# respirho2pilev2.net
KiCad netlist of a schematic drawn in EAGLE
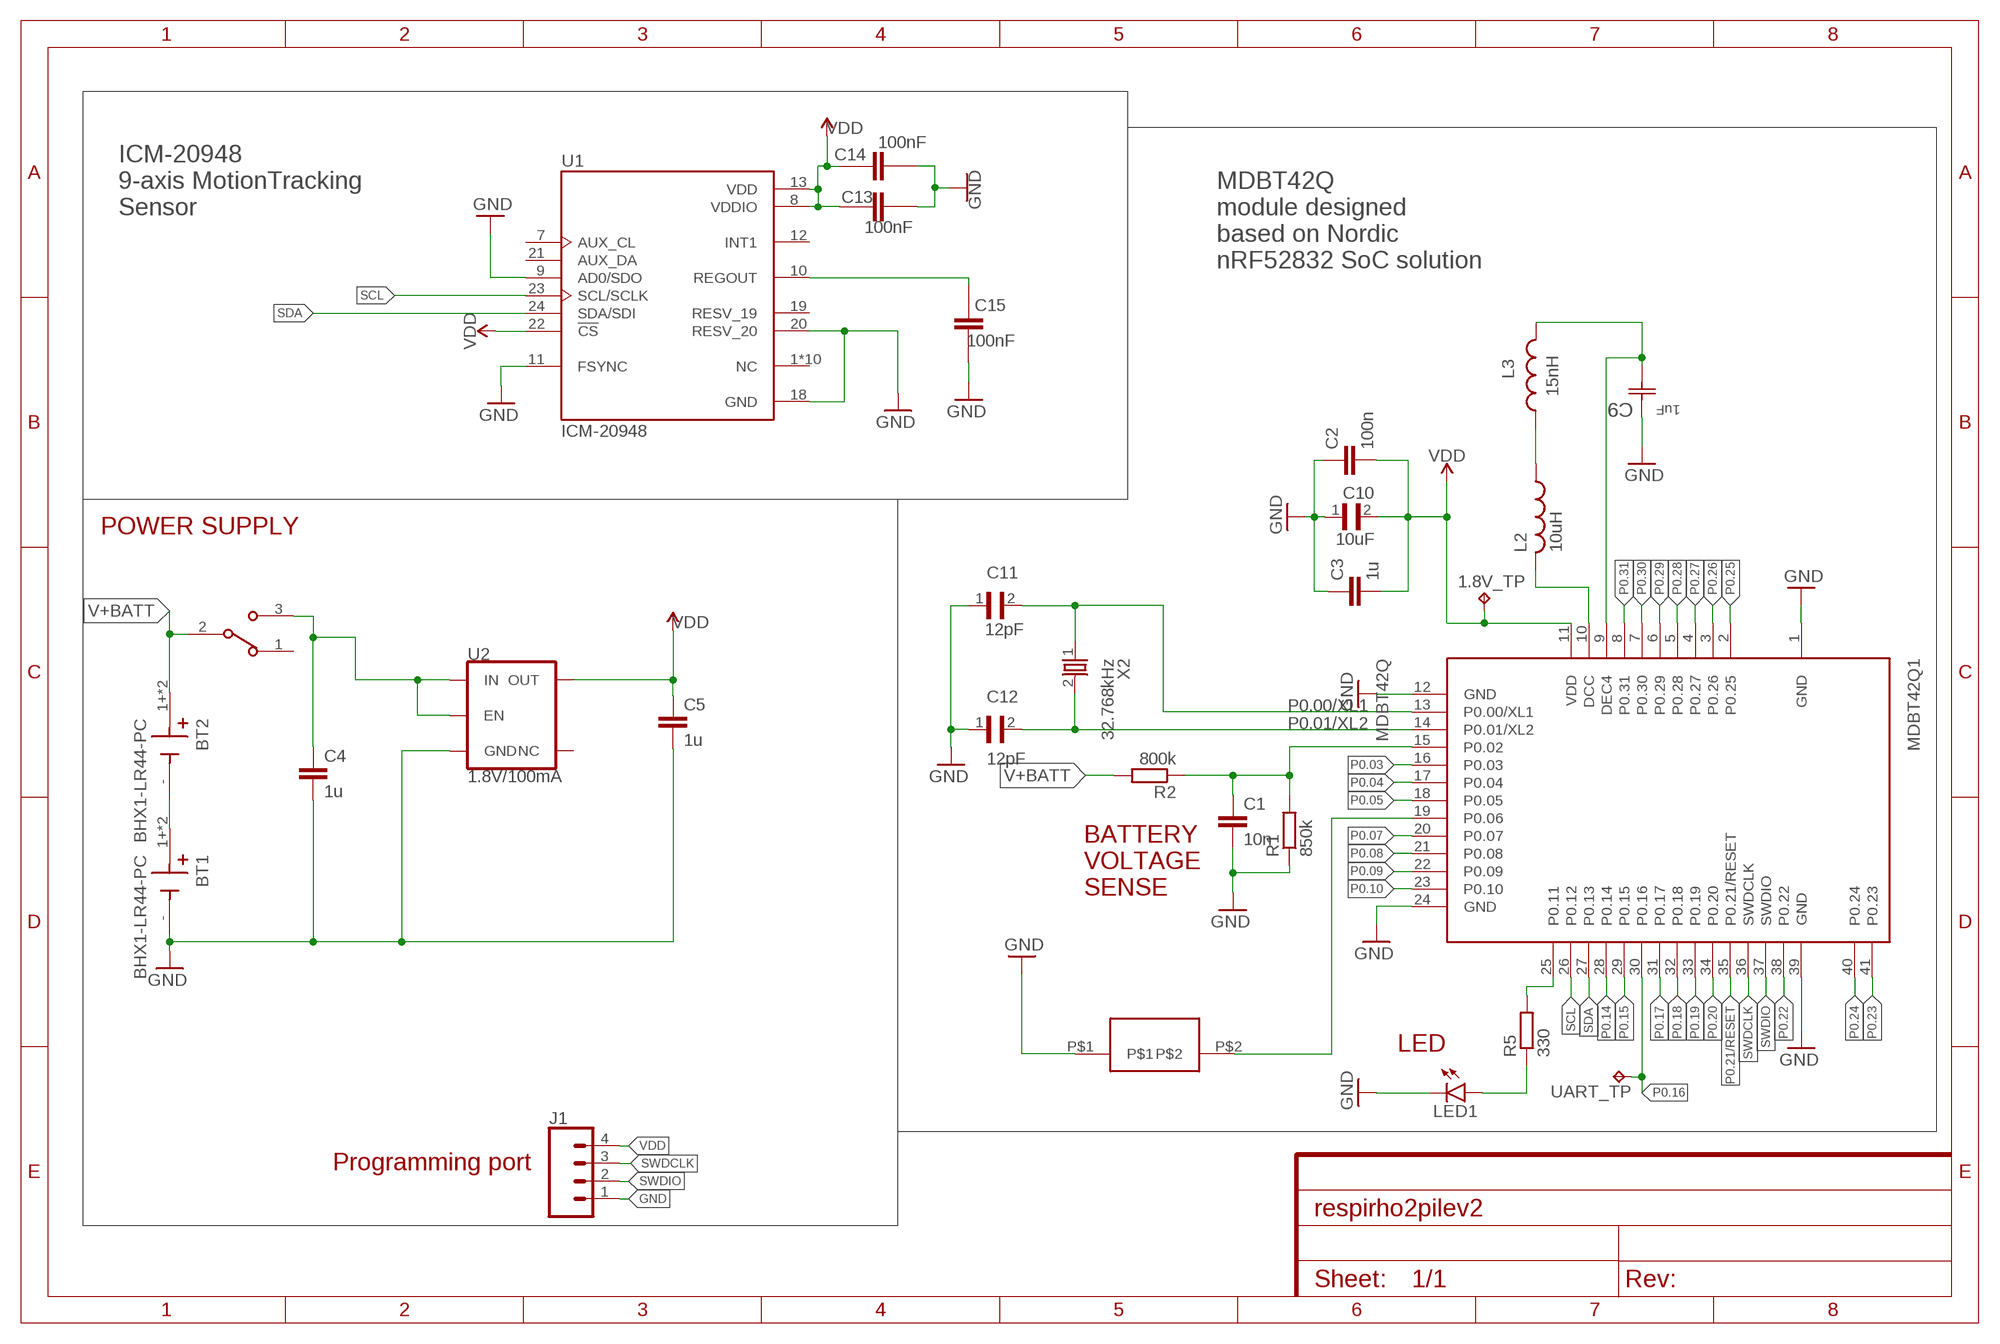
[diagram p0: schematic, sheet 1]

(export (version "E")
  (design (tool "Eeschema 10.0.6"))
  (components
    (comp (ref "1.8V_TP")
      (value "TPB1,27")
      (footprint "eagle-import:B1,27")
      (libsource (lib "eagle-import") (part "TPB1,27"))
    )
    (comp (ref "BT1")
      (value "BHX1-LR44-PC")
      (footprint "eagle-import:BAT_BHX1-LR44-PC")
      (fields (field (name "DIGI-KEY_PART_NUMBER") "BHX1-LR44-PC-G-ND") (field (name "MF") "MPD"))
      (libsource (lib "eagle-import") (part "BHX1-LR44-PC"))
    )
    (comp (ref "BT2")
      (value "BHX1-LR44-PC")
      (footprint "eagle-import:BAT_BHX1-LR44-PC")
      (fields (field (name "DIGI-KEY_PART_NUMBER") "BHX1-LR44-PC-G-ND") (field (name "MF") "MPD"))
      (libsource (lib "eagle-import") (part "BHX1-LR44-PC"))
    )
    (comp (ref "C1")
      (value "10n")
      (footprint "eagle-import:C0603")
      (libsource (lib "eagle-import") (part "C-EUC0603"))
    )
    (comp (ref "C2")
      (value "100n")
      (footprint "eagle-import:C0402")
      (libsource (lib "eagle-import") (part "C-EUC0402"))
    )
    (comp (ref "C3")
      (value "1u")
      (footprint "eagle-import:C0603")
      (libsource (lib "eagle-import") (part "C-EUC0603"))
    )
    (comp (ref "C4")
      (value "1u")
      (footprint "eagle-import:C0402")
      (libsource (lib "eagle-import") (part "C-EUC0402"))
    )
    (comp (ref "C5")
      (value "1u")
      (footprint "eagle-import:C0402")
      (libsource (lib "eagle-import") (part "C-EUC0402"))
    )
    (comp (ref "C9")
      (value "1uF")
      (footprint "eagle-import:CAPC1608X90N")
      (fields
        (field (name "DIGI-KEY_PART_NUMBER") "311-1446-1-ND")
        (field (name "MF") "Yageo")
        (field (name "MP") "CC0603KRX7R7BB105")
      )
      (libsource (lib "eagle-import") (part "CC0603KRX7R7BB105"))
    )
    (comp (ref "C10")
      (value "10uF")
      (footprint "eagle-import:CAPC1608X95N")
      (fields
        (field (name "DIGI-KEY_PART_NUMBER") "490-14372-1-ND")
        (field (name "MF") "Murata")
        (field (name "MP") "GRM188R61A106KE69J")
      )
      (libsource (lib "eagle-import") (part "GRM188R61A106KE69J"))
    )
    (comp (ref "C11")
      (value "12pF")
      (footprint "eagle-import:CAPC1005X56N")
      (fields
        (field (name "DIGI-KEY_PART_NUMBER") "478-7871-1-ND")
        (field (name "MF") "AVX")
        (field (name "MP") "04025A120GAT2A")
      )
      (libsource (lib "eagle-import") (part "04025A120GAT2A"))
    )
    (comp (ref "C12")
      (value "12pF")
      (footprint "eagle-import:CAPC1005X56N")
      (fields
        (field (name "DIGI-KEY_PART_NUMBER") "478-7871-1-ND")
        (field (name "MF") "AVX")
        (field (name "MP") "04025A120GAT2A")
      )
      (libsource (lib "eagle-import") (part "04025A120GAT2A"))
    )
    (comp (ref "C13")
      (value "100nF")
      (footprint "eagle-import:CAPC1005X60")
      (fields
        (field (name "DIGI-KEY_PART_NUMBER") "311-1345-1-ND")
        (field (name "MF") "Yageo")
        (field (name "MP") "CC0402KRX7R6BB104")
      )
      (libsource (lib "eagle-import") (part "CC0402KRX7R6BB104"))
    )
    (comp (ref "C14")
      (value "100nF")
      (footprint "eagle-import:CAPC1005X60")
      (fields
        (field (name "DIGI-KEY_PART_NUMBER") "311-1345-1-ND")
        (field (name "MF") "Yageo")
        (field (name "MP") "CC0402KRX7R6BB104")
      )
      (libsource (lib "eagle-import") (part "CC0402KRX7R6BB104"))
    )
    (comp (ref "C15")
      (value "100nF")
      (footprint "eagle-import:CAPC1005X60")
      (fields
        (field (name "DIGI-KEY_PART_NUMBER") "311-1345-1-ND")
        (field (name "MF") "Yageo")
        (field (name "MP") "CC0402KRX7R6BB104")
      )
      (libsource (lib "eagle-import") (part "CC0402KRX7R6BB104"))
    )
    (comp (ref "J1")
      (value "CONN_04PTH")
      (footprint "eagle-import:1X04")
      (libsource (lib "eagle-import") (part "CONN_04PTH"))
    )
    (comp (ref "L2")
      (value "10uH")
      (footprint "eagle-import:RESC0603_L")
      (libsource (lib "eagle-import") (part "INDUCTOR_0603_L"))
    )
    (comp (ref "L3")
      (value "15nH")
      (footprint "eagle-import:INDC1005X55N")
      (fields
        (field (name "DIGI-KEY_PART_NUMBER") "490-2625-1-ND")
        (field (name "MF") "Murata Electronics")
        (field (name "MP") "LQG15HS15NJ02D")
      )
      (libsource (lib "eagle-import") (part "LQG15HS15NJ02D"))
    )
    (comp (ref "LED1")
      (value "LEDCHIPLED_1206")
      (footprint "eagle-import:CHIPLED_1206")
      (libsource (lib "eagle-import") (part "LEDCHIPLED_1206"))
    )
    (comp (ref "MDBT42Q1")
      (value "MDBT42Q")
      (footprint "eagle-import:MDBT42Q")
      (libsource (lib "eagle-import") (part "MDBT42Q"))
    )
    (comp (ref "R1")
      (value "850k")
      (footprint "eagle-import:R0603")
      (libsource (lib "eagle-import") (part "R-EU_R0603"))
    )
    (comp (ref "R2")
      (value "800k")
      (footprint "eagle-import:R0603")
      (libsource (lib "eagle-import") (part "R-EU_R0603"))
    )
    (comp (ref "R5")
      (value "330")
      (footprint "eagle-import:R0603")
      (libsource (lib "eagle-import") (part "R-EU_R0603"))
    )
    (comp (ref "S2")
      (value "EG1213")
      (footprint "eagle-import:SW_EG1213")
      (fields (field (name "DIGI-KEY_PART_NUMBER") "EG1906-ND") (field (name "MF") "E-Switch"))
      (libsource (lib "eagle-import") (part "EG1213"))
    )
    (comp (ref "U$1")
      (value "KSS231GLFS")
      (footprint "eagle-import:KSS231GLFS")
      (libsource (lib "eagle-import") (part "KSS231GLFS"))
    )
    (comp (ref "U1")
      (value "ICM-20948")
      (footprint "eagle-import:QFN40P300X300X105-24N")
      (fields (field (name "MF") "TDK InvenSense"))
      (libsource (lib "eagle-import") (part "ICM-20948"))
    )
    (comp (ref "U2")
      (value "1.8V/100mA")
      (footprint "eagle-import:SC70")
      (libsource (lib "eagle-import") (part "V_REG_SP6214-1.8V"))
    )
    (comp (ref "UART_TP")
      (value "TPB1,27")
      (footprint "eagle-import:B1,27")
      (libsource (lib "eagle-import") (part "TPB1,27"))
    )
    (comp (ref "X2")
      (value "32.768kHz")
      (footprint "eagle-import:XTAL_3215_N")
      (libsource (lib "eagle-import") (part "XTAL_32KHZ"))
    )
  )
  (nets
    (net (code "1") (name "/P0.00{slash}XL1") (class "Default")
      (node (ref "C11") (pin "2") (pinfunction "2_2") (pintype "passive"))
      (node (ref "MDBT42Q1") (pin "13") (pinfunction "P0.00/XL1_13") (pintype "bidirectional"))
      (node (ref "X2") (pin "1") (pinfunction "1_1") (pintype "passive"))
    )
    (net (code "2") (name "/P0.01{slash}XL2") (class "Default")
      (node (ref "C12") (pin "2") (pinfunction "2_2") (pintype "passive"))
      (node (ref "MDBT42Q1") (pin "14") (pinfunction "P0.01/XL2_14") (pintype "bidirectional"))
      (node (ref "X2") (pin "2") (pinfunction "2_2") (pintype "passive"))
    )
    (net (code "3") (name "GND") (class "Default")
      (node (ref "BT1") (pin "-") (pinfunction "-_-") (pintype "passive"))
      (node (ref "C1") (pin "2") (pinfunction "2_2") (pintype "passive"))
      (node (ref "C10") (pin "1") (pinfunction "1_1") (pintype "passive"))
      (node (ref "C11") (pin "1") (pinfunction "1_1") (pintype "passive"))
      (node (ref "C12") (pin "1") (pinfunction "1_1") (pintype "passive"))
      (node (ref "C13") (pin "1") (pinfunction "1_1") (pintype "passive"))
      (node (ref "C14") (pin "1") (pinfunction "1_1") (pintype "passive"))
      (node (ref "C15") (pin "1") (pinfunction "1_1") (pintype "passive"))
      (node (ref "C2") (pin "1") (pinfunction "1_1") (pintype "passive"))
      (node (ref "C3") (pin "1") (pinfunction "1_1") (pintype "passive"))
      (node (ref "C4") (pin "2") (pinfunction "2_2") (pintype "passive"))
      (node (ref "C5") (pin "2") (pinfunction "2_2") (pintype "passive"))
      (node (ref "C9") (pin "1") (pinfunction "C1_1") (pintype "passive"))
      (node (ref "J1") (pin "1") (pinfunction "1_1") (pintype "passive"))
      (node (ref "LED1") (pin "C") (pinfunction "C_C") (pintype "passive"))
      (node (ref "MDBT42Q1") (pin "1") (pinfunction "GND_1") (pintype "bidirectional"))
      (node (ref "MDBT42Q1") (pin "12") (pinfunction "GND_12") (pintype "bidirectional"))
      (node (ref "MDBT42Q1") (pin "24") (pinfunction "GND_24") (pintype "bidirectional"))
      (node (ref "MDBT42Q1") (pin "39") (pinfunction "GND_39") (pintype "bidirectional"))
      (node (ref "R1") (pin "1") (pinfunction "1_1") (pintype "passive"))
      (node (ref "U$1") (pin "P$1") (pinfunction "P$1_P$1") (pintype "bidirectional"))
      (node (ref "U1") (pin "11") (pinfunction "FSYNC_11") (pintype "input"))
      (node (ref "U1") (pin "18") (pinfunction "GND_18") (pintype "power_in"))
      (node (ref "U1") (pin "20") (pinfunction "RESV_20_20") (pintype "passive"))
      (node (ref "U1") (pin "9") (pinfunction "AD0/SDO_9") (pintype "bidirectional"))
      (node (ref "U2") (pin "2") (pinfunction "GND_2") (pintype "input"))
    )
    (net (code "4") (name "Net-(BT1-+-Pad1+)") (class "Default")
      (node (ref "BT1") (pin "1+") (pinfunction "+_1+") (pintype "passive"))
      (node (ref "BT1") (pin "2+") (pinfunction "+_2+") (pintype "passive"))
      (node (ref "BT2") (pin "-") (pinfunction "-_-") (pintype "passive"))
    )
    (net (code "5") (name "Net-(C9-C2)") (class "Default")
      (node (ref "C9") (pin "2") (pinfunction "C2_2") (pintype "passive"))
      (node (ref "L3") (pin "2") (pinfunction "2_2") (pintype "passive"))
      (node (ref "MDBT42Q1") (pin "9") (pinfunction "DEC4_9") (pintype "bidirectional"))
    )
    (net (code "6") (name "Net-(L2-Pad1)") (class "Default")
      (node (ref "L2") (pin "1") (pinfunction "1_1") (pintype "passive"))
      (node (ref "L3") (pin "1") (pinfunction "1_1") (pintype "passive"))
    )
    (net (code "7") (name "Net-(LED1-PadA)") (class "Default")
      (node (ref "LED1") (pin "A") (pinfunction "A_A") (pintype "passive"))
      (node (ref "R5") (pin "1") (pinfunction "1_1") (pintype "passive"))
    )
    (net (code "8") (name "Net-(MDBT42Q1-DCC)") (class "Default")
      (node (ref "L2") (pin "2") (pinfunction "2_2") (pintype "passive"))
      (node (ref "MDBT42Q1") (pin "10") (pinfunction "DCC_10") (pintype "bidirectional"))
    )
    (net (code "9") (name "Net-(MDBT42Q1-P0.02)") (class "Default")
      (node (ref "C1") (pin "1") (pinfunction "1_1") (pintype "passive"))
      (node (ref "MDBT42Q1") (pin "15") (pinfunction "P0.02_15") (pintype "bidirectional"))
      (node (ref "R1") (pin "2") (pinfunction "2_2") (pintype "passive"))
      (node (ref "R2") (pin "1") (pinfunction "1_1") (pintype "passive"))
    )
    (net (code "10") (name "Net-(MDBT42Q1-P0.06)") (class "Default")
      (node (ref "MDBT42Q1") (pin "19") (pinfunction "P0.06_19") (pintype "bidirectional"))
      (node (ref "U$1") (pin "P$2") (pinfunction "P$2_P$2") (pintype "bidirectional"))
    )
    (net (code "11") (name "Net-(MDBT42Q1-P0.11)") (class "Default")
      (node (ref "MDBT42Q1") (pin "25") (pinfunction "P0.11_25") (pintype "bidirectional"))
      (node (ref "R5") (pin "2") (pinfunction "2_2") (pintype "passive"))
    )
    (net (code "12") (name "Net-(U1-REGOUT)") (class "Default")
      (node (ref "C15") (pin "2") (pinfunction "2_2") (pintype "passive"))
      (node (ref "U1") (pin "10") (pinfunction "REGOUT_10") (pintype "output"))
    )
    (net (code "13") (name "Net-(U2-EN)") (class "Default")
      (node (ref "C4") (pin "1") (pinfunction "1_1") (pintype "passive"))
      (node (ref "S2") (pin "3") (pinfunction "3_3") (pintype "passive"))
      (node (ref "U2") (pin "1") (pinfunction "IN_1") (pintype "input"))
      (node (ref "U2") (pin "3") (pinfunction "EN_3") (pintype "input"))
    )
    (net (code "14") (name "P0.03") (class "Default")
      (node (ref "MDBT42Q1") (pin "16") (pinfunction "P0.03_16") (pintype "bidirectional"))
    )
    (net (code "15") (name "P0.04") (class "Default")
      (node (ref "MDBT42Q1") (pin "17") (pinfunction "P0.04_17") (pintype "bidirectional"))
    )
    (net (code "16") (name "P0.05") (class "Default")
      (node (ref "MDBT42Q1") (pin "18") (pinfunction "P0.05_18") (pintype "bidirectional"))
    )
    (net (code "17") (name "P0.07") (class "Default")
      (node (ref "MDBT42Q1") (pin "20") (pinfunction "P0.07_20") (pintype "bidirectional"))
    )
    (net (code "18") (name "P0.08") (class "Default")
      (node (ref "MDBT42Q1") (pin "21") (pinfunction "P0.08_21") (pintype "bidirectional"))
    )
    (net (code "19") (name "P0.09") (class "Default")
      (node (ref "MDBT42Q1") (pin "22") (pinfunction "P0.09_22") (pintype "bidirectional"))
    )
    (net (code "20") (name "P0.10") (class "Default")
      (node (ref "MDBT42Q1") (pin "23") (pinfunction "P0.10_23") (pintype "bidirectional"))
    )
    (net (code "21") (name "P0.14") (class "Default")
      (node (ref "MDBT42Q1") (pin "28") (pinfunction "P0.14_28") (pintype "bidirectional"))
    )
    (net (code "22") (name "P0.15") (class "Default")
      (node (ref "MDBT42Q1") (pin "29") (pinfunction "P0.15_29") (pintype "bidirectional"))
    )
    (net (code "23") (name "P0.16") (class "Default")
      (node (ref "MDBT42Q1") (pin "30") (pinfunction "P0.16_30") (pintype "bidirectional"))
      (node (ref "UART_TP") (pin "TP") (pinfunction "TP_TP") (pintype "input"))
    )
    (net (code "24") (name "P0.17") (class "Default")
      (node (ref "MDBT42Q1") (pin "31") (pinfunction "P0.17_31") (pintype "bidirectional"))
    )
    (net (code "25") (name "P0.18") (class "Default")
      (node (ref "MDBT42Q1") (pin "32") (pinfunction "P0.18_32") (pintype "bidirectional"))
    )
    (net (code "26") (name "P0.19") (class "Default")
      (node (ref "MDBT42Q1") (pin "33") (pinfunction "P0.19_33") (pintype "bidirectional"))
    )
    (net (code "27") (name "P0.20") (class "Default")
      (node (ref "MDBT42Q1") (pin "34") (pinfunction "P0.20_34") (pintype "bidirectional"))
    )
    (net (code "28") (name "P0.21{slash}RESET") (class "Default")
      (node (ref "MDBT42Q1") (pin "35") (pinfunction "P0.21/RESET_35") (pintype "bidirectional"))
    )
    (net (code "29") (name "P0.22") (class "Default")
      (node (ref "MDBT42Q1") (pin "38") (pinfunction "P0.22_38") (pintype "bidirectional"))
    )
    (net (code "30") (name "P0.23") (class "Default")
      (node (ref "MDBT42Q1") (pin "41") (pinfunction "P0.23_41") (pintype "bidirectional"))
    )
    (net (code "31") (name "P0.24") (class "Default")
      (node (ref "MDBT42Q1") (pin "40") (pinfunction "P0.24_40") (pintype "bidirectional"))
    )
    (net (code "32") (name "P0.25") (class "Default")
      (node (ref "MDBT42Q1") (pin "2") (pinfunction "P0.25_2") (pintype "bidirectional"))
    )
    (net (code "33") (name "P0.26") (class "Default")
      (node (ref "MDBT42Q1") (pin "3") (pinfunction "P0.26_3") (pintype "bidirectional"))
    )
    (net (code "34") (name "P0.27") (class "Default")
      (node (ref "MDBT42Q1") (pin "4") (pinfunction "P0.27_4") (pintype "bidirectional"))
    )
    (net (code "35") (name "P0.28") (class "Default")
      (node (ref "MDBT42Q1") (pin "5") (pinfunction "P0.28_5") (pintype "bidirectional"))
    )
    (net (code "36") (name "P0.29") (class "Default")
      (node (ref "MDBT42Q1") (pin "6") (pinfunction "P0.29_6") (pintype "bidirectional"))
    )
    (net (code "37") (name "P0.30") (class "Default")
      (node (ref "MDBT42Q1") (pin "7") (pinfunction "P0.30_7") (pintype "bidirectional"))
    )
    (net (code "38") (name "P0.31") (class "Default")
      (node (ref "MDBT42Q1") (pin "8") (pinfunction "P0.31_8") (pintype "bidirectional"))
    )
    (net (code "39") (name "SCL") (class "Default")
      (node (ref "MDBT42Q1") (pin "26") (pinfunction "P0.12_26") (pintype "bidirectional"))
      (node (ref "U1") (pin "23") (pinfunction "SCL/SCLK_23") (pintype "input"))
    )
    (net (code "40") (name "SDA") (class "Default")
      (node (ref "MDBT42Q1") (pin "27") (pinfunction "P0.13_27") (pintype "bidirectional"))
      (node (ref "U1") (pin "24") (pinfunction "SDA/SDI_24") (pintype "bidirectional"))
    )
    (net (code "41") (name "SWDCLK") (class "Default")
      (node (ref "J1") (pin "3") (pinfunction "3_3") (pintype "passive"))
      (node (ref "MDBT42Q1") (pin "36") (pinfunction "SWDCLK_36") (pintype "bidirectional"))
    )
    (net (code "42") (name "SWDIO") (class "Default")
      (node (ref "J1") (pin "2") (pinfunction "2_2") (pintype "passive"))
      (node (ref "MDBT42Q1") (pin "37") (pinfunction "SWDIO_37") (pintype "bidirectional"))
    )
    (net (code "43") (name "V+BATT") (class "Default")
      (node (ref "BT2") (pin "1+") (pinfunction "+_1+") (pintype "passive"))
      (node (ref "BT2") (pin "2+") (pinfunction "+_2+") (pintype "passive"))
      (node (ref "R2") (pin "2") (pinfunction "2_2") (pintype "passive"))
      (node (ref "S2") (pin "2") (pinfunction "2_2") (pintype "passive"))
    )
    (net (code "44") (name "VDD") (class "Default")
      (node (ref "1.8V_TP") (pin "TP") (pinfunction "TP_TP") (pintype "input"))
      (node (ref "C10") (pin "2") (pinfunction "2_2") (pintype "passive"))
      (node (ref "C13") (pin "2") (pinfunction "2_2") (pintype "passive"))
      (node (ref "C14") (pin "2") (pinfunction "2_2") (pintype "passive"))
      (node (ref "C2") (pin "2") (pinfunction "2_2") (pintype "passive"))
      (node (ref "C3") (pin "2") (pinfunction "2_2") (pintype "passive"))
      (node (ref "C5") (pin "1") (pinfunction "1_1") (pintype "passive"))
      (node (ref "J1") (pin "4") (pinfunction "4_4") (pintype "passive"))
      (node (ref "MDBT42Q1") (pin "11") (pinfunction "VDD_11") (pintype "bidirectional"))
      (node (ref "U1") (pin "13") (pinfunction "VDD_13") (pintype "power_in"))
      (node (ref "U1") (pin "22") (pinfunction "~{CS}_22") (pintype "input"))
      (node (ref "U1") (pin "8") (pinfunction "VDDIO_8") (pintype "power_in"))
      (node (ref "U2") (pin "5") (pinfunction "OUT_5") (pintype "passive"))
    )
    (net (code "45") (name "unconnected-(S2-Pad1)") (class "Default")
      (node (ref "S2") (pin "1") (pinfunction "1_1") (pintype "passive"))
    )
    (net (code "46") (name "unconnected-(U1-AUX_CL-Pad7)") (class "Default")
      (node (ref "U1") (pin "7") (pinfunction "AUX_CL_7") (pintype "input"))
    )
    (net (code "47") (name "unconnected-(U1-AUX_DA-Pad21)") (class "Default")
      (node (ref "U1") (pin "21") (pinfunction "AUX_DA_21") (pintype "bidirectional"))
    )
    (net (code "48") (name "unconnected-(U1-INT1-Pad12)") (class "Default")
      (node (ref "U1") (pin "12") (pinfunction "INT1_12") (pintype "output"))
    )
    (net (code "49") (name "unconnected-(U1-NC-Pad1)") (class "Default")
      (node (ref "U1") (pin "1") (pinfunction "NC_1") (pintype "no_connect"))
    )
    (net (code "50") (name "unconnected-(U1-NC-Pad2)") (class "Default")
      (node (ref "U1") (pin "2") (pinfunction "NC_2") (pintype "no_connect"))
    )
    (net (code "51") (name "unconnected-(U1-NC-Pad3)") (class "Default")
      (node (ref "U1") (pin "3") (pinfunction "NC_3") (pintype "no_connect"))
    )
    (net (code "52") (name "unconnected-(U1-NC-Pad4)") (class "Default")
      (node (ref "U1") (pin "4") (pinfunction "NC_4") (pintype "no_connect"))
    )
    (net (code "53") (name "unconnected-(U1-NC-Pad5)") (class "Default")
      (node (ref "U1") (pin "5") (pinfunction "NC_5") (pintype "no_connect"))
    )
    (net (code "54") (name "unconnected-(U1-NC-Pad6)") (class "Default")
      (node (ref "U1") (pin "6") (pinfunction "NC_6") (pintype "no_connect"))
    )
    (net (code "55") (name "unconnected-(U1-NC-Pad14)") (class "Default")
      (node (ref "U1") (pin "14") (pinfunction "NC_14") (pintype "no_connect"))
    )
    (net (code "56") (name "unconnected-(U1-NC-Pad15)") (class "Default")
      (node (ref "U1") (pin "15") (pinfunction "NC_15") (pintype "no_connect"))
    )
    (net (code "57") (name "unconnected-(U1-NC-Pad16)") (class "Default")
      (node (ref "U1") (pin "16") (pinfunction "NC_16") (pintype "no_connect"))
    )
    (net (code "58") (name "unconnected-(U1-NC-Pad17)") (class "Default")
      (node (ref "U1") (pin "17") (pinfunction "NC_17") (pintype "no_connect"))
    )
    (net (code "59") (name "unconnected-(U1-RESV_19-Pad19)") (class "Default")
      (node (ref "U1") (pin "19") (pinfunction "RESV_19_19") (pintype "passive"))
    )
    (net (code "60") (name "unconnected-(U2-NC-Pad4)") (class "Default")
      (node (ref "U2") (pin "4") (pinfunction "NC_4") (pintype "no_connect"))
    )
  )
)
